# Raspberry_Pi_CM4_Periphery.net
KiCad netlist of a schematic drawn in Altium Designer
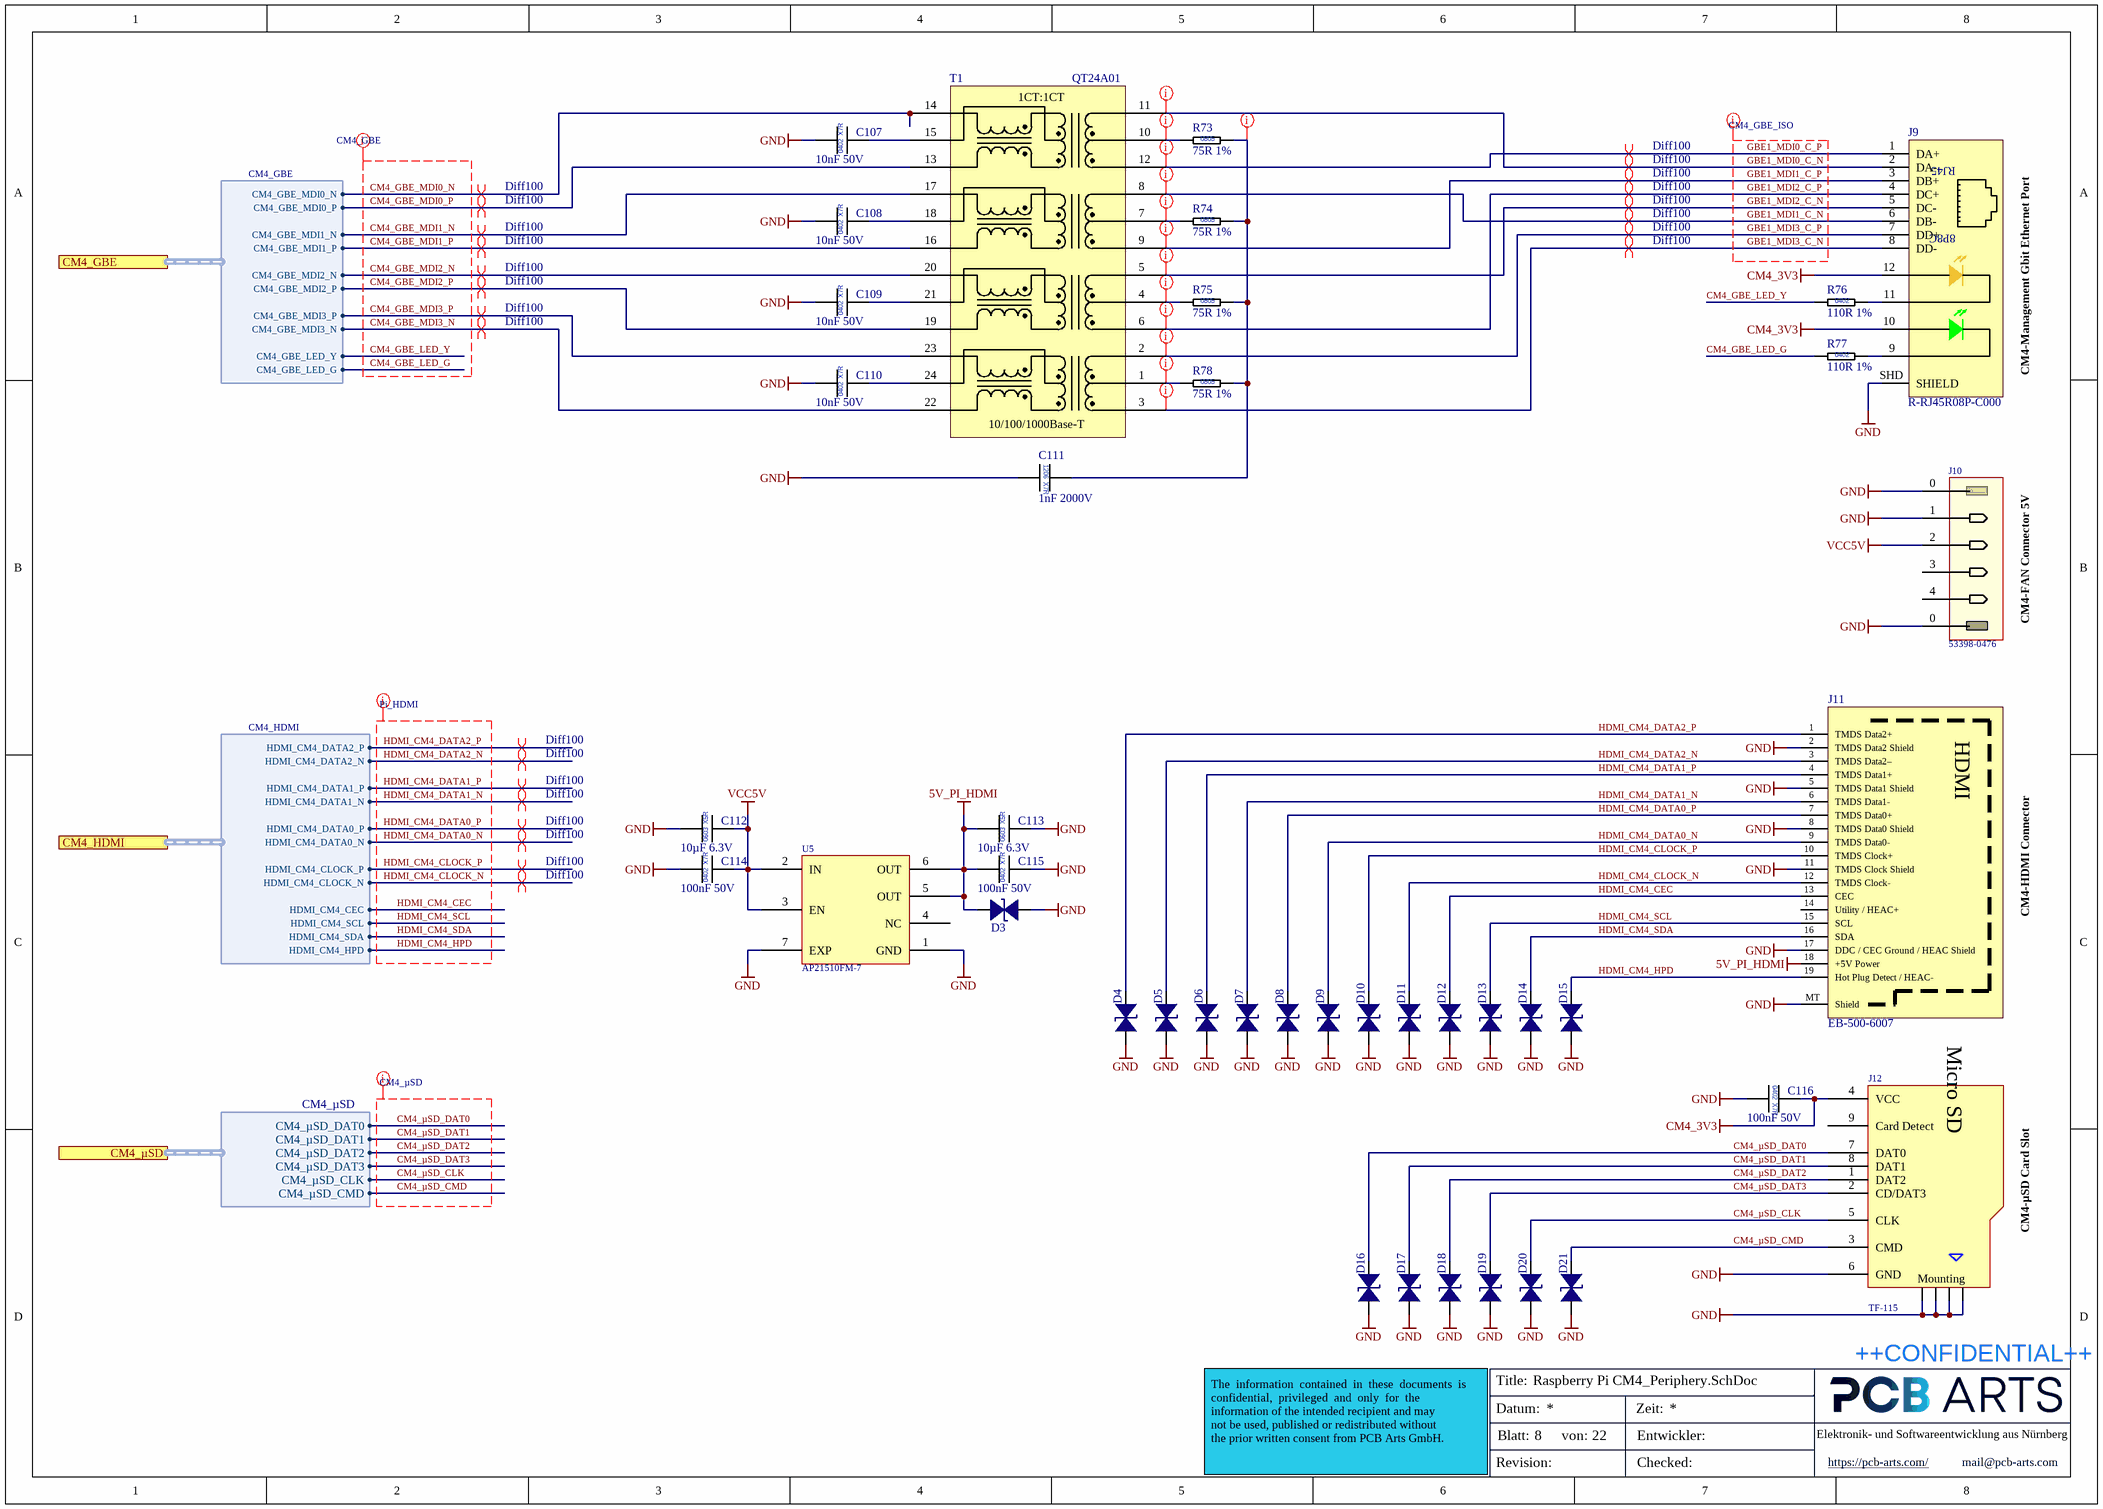
[diagram p0: Raspberry Pi CM4_Periphery.SchDoc]

(export (version "E")
  (design (tool "Eeschema 10.0.6"))
  (components
    (comp (ref "C107")
      (value "10nF 50V")
      (footprint "Cap:CAP_0402_L")
      (description "Multilayer Ceramic Capacitors MLCC - SMD/SMT 0402 50VDC")
      (libsource (lib "Cap") (part "CAP_0402_10nF_50V"))
    )
    (comp (ref "C108")
      (value "10nF 50V")
      (footprint "Cap:CAP_0402_L")
      (description "Multilayer Ceramic Capacitors MLCC - SMD/SMT 0402 50VDC")
      (libsource (lib "Cap") (part "CAP_0402_10nF_50V"))
    )
    (comp (ref "C109")
      (value "10nF 50V")
      (footprint "Cap:CAP_0402_L")
      (description "Multilayer Ceramic Capacitors MLCC - SMD/SMT 0402 50VDC")
      (libsource (lib "Cap") (part "CAP_0402_10nF_50V"))
    )
    (comp (ref "C110")
      (value "10nF 50V")
      (footprint "Cap:CAP_0402_L")
      (description "Multilayer Ceramic Capacitors MLCC - SMD/SMT 0402 50VDC")
      (libsource (lib "Cap") (part "CAP_0402_10nF_50V"))
    )
    (comp (ref "C111")
      (value "1nF 2000V")
      (footprint "Cap:CAP_1206")
      (description "Multilayer Ceramic Capacitors MLCC - SMD/SMT 1206 2000VDC")
      (libsource (lib "Cap") (part "CAP_1206_1nF_2000V"))
    )
    (comp (ref "C112")
      (value "10µF 6.3V")
      (footprint "Cap:CAP_0603_L")
      (description "Multilayer Ceramic Capacitors MLCC - SMD/SMT 0603 6.3VDC")
      (libsource (lib "Cap") (part "CAP_0603_10µF_6.3V"))
    )
    (comp (ref "C113")
      (value "10µF 6.3V")
      (footprint "Cap:CAP_0603_L")
      (description "Multilayer Ceramic Capacitors MLCC - SMD/SMT 0603 6.3VDC")
      (libsource (lib "Cap") (part "CAP_0603_10µF_6.3V"))
    )
    (comp (ref "C114")
      (value "100nF 50V")
      (footprint "Cap:CAP_0402_L")
      (description "Multilayer Ceramic Capacitors MLCC - SMD/SMT 0402 50VDC")
      (libsource (lib "Cap") (part "CAP_0402_100nF_50V"))
    )
    (comp (ref "C115")
      (value "100nF 50V")
      (footprint "Cap:CAP_0402_L")
      (description "Multilayer Ceramic Capacitors MLCC - SMD/SMT 0402 50VDC")
      (libsource (lib "Cap") (part "CAP_0402_100nF_50V"))
    )
    (comp (ref "C116")
      (value "100nF 50V")
      (footprint "Cap:CAP_0402_L")
      (description "Multilayer Ceramic Capacitors MLCC - SMD/SMT 0402 50VDC")
      (libsource (lib "") (part "CAP_0402_100nF_50V_1"))
    )
    (comp (ref "D3")
      (value "CESDP0402UC5VB")
      (footprint "Protec:TVS_0402")
      (description "Low Capacitance ESD Protection Diode 0402")
      (libsource (lib "Protec") (part "CESDP0402UC5VB_TVS Diode 0402"))
    )
    (comp (ref "D4")
      (value "CESDP0402UC5VB")
      (footprint "Protec:TVS_0402")
      (description "Low Capacitance ESD Protection Diode 0402")
      (libsource (lib "Protec") (part "CESDP0402UC5VB_TVS Diode 0402"))
    )
    (comp (ref "D5")
      (value "CESDP0402UC5VB")
      (footprint "Protec:TVS_0402")
      (description "Low Capacitance ESD Protection Diode 0402")
      (libsource (lib "Protec") (part "CESDP0402UC5VB_TVS Diode 0402"))
    )
    (comp (ref "D6")
      (value "CESDP0402UC5VB")
      (footprint "Protec:TVS_0402")
      (description "Low Capacitance ESD Protection Diode 0402")
      (libsource (lib "Protec") (part "CESDP0402UC5VB_TVS Diode 0402"))
    )
    (comp (ref "D7")
      (value "CESDP0402UC5VB")
      (footprint "Protec:TVS_0402")
      (description "Low Capacitance ESD Protection Diode 0402")
      (libsource (lib "Protec") (part "CESDP0402UC5VB_TVS Diode 0402"))
    )
    (comp (ref "D8")
      (value "CESDP0402UC5VB")
      (footprint "Protec:TVS_0402")
      (description "Low Capacitance ESD Protection Diode 0402")
      (libsource (lib "Protec") (part "CESDP0402UC5VB_TVS Diode 0402"))
    )
    (comp (ref "D9")
      (value "CESDP0402UC5VB")
      (footprint "Protec:TVS_0402")
      (description "Low Capacitance ESD Protection Diode 0402")
      (libsource (lib "Protec") (part "CESDP0402UC5VB_TVS Diode 0402"))
    )
    (comp (ref "D10")
      (value "CESDP0402UC5VB")
      (footprint "Protec:TVS_0402")
      (description "Low Capacitance ESD Protection Diode 0402")
      (libsource (lib "Protec") (part "CESDP0402UC5VB_TVS Diode 0402"))
    )
    (comp (ref "D11")
      (value "CESDP0402UC5VB")
      (footprint "Protec:TVS_0402")
      (description "Low Capacitance ESD Protection Diode 0402")
      (libsource (lib "Protec") (part "CESDP0402UC5VB_TVS Diode 0402"))
    )
    (comp (ref "D12")
      (value "CESDP0402UC5VB")
      (footprint "Protec:TVS_0402")
      (description "Low Capacitance ESD Protection Diode 0402")
      (libsource (lib "Protec") (part "CESDP0402UC5VB_TVS Diode 0402"))
    )
    (comp (ref "D13")
      (value "CESDP0402UC5VB")
      (footprint "Protec:TVS_0402")
      (description "Low Capacitance ESD Protection Diode 0402")
      (libsource (lib "Protec") (part "CESDP0402UC5VB_TVS Diode 0402"))
    )
    (comp (ref "D14")
      (value "CESDP0402UC5VB")
      (footprint "Protec:TVS_0402")
      (description "Low Capacitance ESD Protection Diode 0402")
      (libsource (lib "Protec") (part "CESDP0402UC5VB_TVS Diode 0402"))
    )
    (comp (ref "D15")
      (value "CESDP0402UC5VB")
      (footprint "Protec:TVS_0402")
      (description "Low Capacitance ESD Protection Diode 0402")
      (libsource (lib "Protec") (part "CESDP0402UC5VB_TVS Diode 0402"))
    )
    (comp (ref "D16")
      (value "CESDP0402UC5VB")
      (footprint "Protec:TVS_0402")
      (description "Low Capacitance ESD Protection Diode 0402")
      (libsource (lib "Protec") (part "CESDP0402UC5VB_TVS Diode 0402"))
    )
    (comp (ref "D17")
      (value "CESDP0402UC5VB")
      (footprint "Protec:TVS_0402")
      (description "Low Capacitance ESD Protection Diode 0402")
      (libsource (lib "Protec") (part "CESDP0402UC5VB_TVS Diode 0402"))
    )
    (comp (ref "D18")
      (value "CESDP0402UC5VB")
      (footprint "Protec:TVS_0402")
      (description "Low Capacitance ESD Protection Diode 0402")
      (libsource (lib "Protec") (part "CESDP0402UC5VB_TVS Diode 0402"))
    )
    (comp (ref "D19")
      (value "CESDP0402UC5VB")
      (footprint "Protec:TVS_0402")
      (description "Low Capacitance ESD Protection Diode 0402")
      (libsource (lib "Protec") (part "CESDP0402UC5VB_TVS Diode 0402"))
    )
    (comp (ref "D20")
      (value "CESDP0402UC5VB")
      (footprint "Protec:TVS_0402")
      (description "Low Capacitance ESD Protection Diode 0402")
      (libsource (lib "Protec") (part "CESDP0402UC5VB_TVS Diode 0402"))
    )
    (comp (ref "D21")
      (value "CESDP0402UC5VB")
      (footprint "Protec:TVS_0402")
      (description "Low Capacitance ESD Protection Diode 0402")
      (libsource (lib "Protec") (part "CESDP0402UC5VB_TVS Diode 0402"))
    )
    (comp (ref "J9")
      (value "R-RJ45R08P-C000")
      (footprint "Conn:Ckmtw - R-RJ45R08P-C000")
      (libsource (lib "Conn") (part "R-RJ45R08P-C000_RJ45 8P8C Shielded Yellow - Green Through Hole Ethernet Connectors"))
    )
    (comp (ref "J10")
      (value "53398-0476")
      (footprint "Conn:Molex 53398-0476")
      (description "1.25mm Pitch, PicoBlade PCB Header, Single Row, horizontal, SMD, 4 Pin")
      (libsource (lib "Conn") (part "53398-0476_1.25mm Pitch, PicoBlade PCB Header, Single Row, horizontal, SMD, 4 Pin"))
    )
    (comp (ref "J11")
      (value "EB-500-6007")
      (footprint "Conn:Elecbee EB-500-6007")
      (description "HDMI Connector Female Vertical 19 Pin")
      (libsource (lib "Conn") (part "EB-500-6007_HDMI Connector 19Pin Vertical THT"))
    )
    (comp (ref "J12")
      (value "TF-115")
      (footprint "conn:TF-115")
      (description "microSD™ Memory Card 8 connector&Ejector 14.5x14.75x1.85mm Card Sockets Connector")
      (libsource (lib "Conn") (part "TF-115_microSD™ Memory Card 8 connector"))
    )
    (comp (ref "R73")
      (value "75R 1%")
      (footprint "Res:RES_0805")
      (description "Thick Film Resistors - SMD 75Ohm 1%")
      (libsource (lib "Res") (part "RES_0805_75R_1%"))
    )
    (comp (ref "R74")
      (value "75R 1%")
      (footprint "Res:RES_0805")
      (description "Thick Film Resistors - SMD 75Ohm 1%")
      (libsource (lib "Res") (part "RES_0805_75R_1%"))
    )
    (comp (ref "R75")
      (value "75R 1%")
      (footprint "Res:RES_0805")
      (description "Thick Film Resistors - SMD 75Ohm 1%")
      (libsource (lib "Res") (part "RES_0805_75R_1%"))
    )
    (comp (ref "R76")
      (value "110R 1%")
      (footprint "Res:RES_0402_L")
      (description "Thick Film Resistors - SMD 110Ohm 1%")
      (libsource (lib "Res") (part "RES_0402_110R_1%"))
    )
    (comp (ref "R77")
      (value "110R 1%")
      (footprint "Res:RES_0402_L")
      (description "Thick Film Resistors - SMD 110Ohm 1%")
      (libsource (lib "Res") (part "RES_0402_110R_1%"))
    )
    (comp (ref "R78")
      (value "75R 1%")
      (footprint "Res:RES_0805")
      (description "Thick Film Resistors - SMD 75Ohm 1%")
      (libsource (lib "Res") (part "RES_0805_75R_1%"))
    )
    (comp (ref "T1")
      (value "QT24A01")
      (footprint "Indc:QT24A01")
      (description "1:1 350 28 1.2 -1 -16 SMD,24PIN RJ45 Transformer RoHS")
      (libsource (lib "Indc") (part "QT24A01_10/100/1000Base-T  Single  Port  Transformer"))
    )
    (comp (ref "U5")
      (value "AP21510FM-7")
      (footprint "Power:QFN50P201X181X60_HS-7N")
      (description "Power Switch ICs - Power Distribution 0.5A SGL Ch USB 2.0 Curr Limited Switch")
      (libsource (lib "Power") (part "AP21510FM-7_Power Switch ICs - Power Distribution Load Switch"))
    )
  )
  (nets
    (net (code "4") (name "/CM4_GBE_LED_G") (class "Default")
      (node (ref "R77") (pin "1") (pinfunction "1_1") (pintype "passive"))
    )
    (net (code "5") (name "/CM4_GBE_LED_Y") (class "Default")
      (node (ref "R76") (pin "1") (pinfunction "1_1") (pintype "passive"))
    )
    (net (code "6") (name "/CM4_GBE_MDI0_N") (class "Default")
      (node (ref "T1") (pin "14") (pinfunction "MX4+_14") (pintype "passive"))
    )
    (net (code "7") (name "/CM4_GBE_MDI0_P") (class "Default")
      (node (ref "T1") (pin "13") (pinfunction "MX4-_13") (pintype "passive"))
    )
    (net (code "8") (name "/CM4_GBE_MDI1_N") (class "Default")
      (node (ref "T1") (pin "17") (pinfunction "MX3+_17") (pintype "passive"))
    )
    (net (code "9") (name "/CM4_GBE_MDI1_P") (class "Default")
      (node (ref "T1") (pin "16") (pinfunction "MX3-_16") (pintype "passive"))
    )
    (net (code "10") (name "/CM4_GBE_MDI2_N") (class "Default")
      (node (ref "T1") (pin "20") (pinfunction "MX2+_20") (pintype "passive"))
    )
    (net (code "11") (name "/CM4_GBE_MDI2_P") (class "Default")
      (node (ref "T1") (pin "19") (pinfunction "MX2-_19") (pintype "passive"))
    )
    (net (code "12") (name "/CM4_GBE_MDI3_N") (class "Default")
      (node (ref "T1") (pin "22") (pinfunction "MX1-_22") (pintype "passive"))
    )
    (net (code "13") (name "/CM4_GBE_MDI3_P") (class "Default")
      (node (ref "T1") (pin "23") (pinfunction "MX1+_23") (pintype "passive"))
    )
    (net (code "14") (name "/CM4_µSD_CLK") (class "Default")
      (node (ref "D20") (pin "2") (pinfunction "2_2") (pintype "passive"))
      (node (ref "J12") (pin "5") (pinfunction "CLK_5") (pintype "passive"))
    )
    (net (code "15") (name "/CM4_µSD_CMD") (class "Default")
      (node (ref "D21") (pin "2") (pinfunction "2_2") (pintype "passive"))
      (node (ref "J12") (pin "3") (pinfunction "CMD_3") (pintype "passive"))
    )
    (net (code "16") (name "/CM4_µSD_DAT0") (class "Default")
      (node (ref "D16") (pin "2") (pinfunction "2_2") (pintype "passive"))
      (node (ref "J12") (pin "7") (pinfunction "DAT0_7") (pintype "passive"))
    )
    (net (code "17") (name "/CM4_µSD_DAT1") (class "Default")
      (node (ref "D17") (pin "2") (pinfunction "2_2") (pintype "passive"))
      (node (ref "J12") (pin "8") (pinfunction "DAT1_8") (pintype "passive"))
    )
    (net (code "18") (name "/CM4_µSD_DAT2") (class "Default")
      (node (ref "D18") (pin "2") (pinfunction "2_2") (pintype "passive"))
      (node (ref "J12") (pin "1") (pinfunction "DAT2_1") (pintype "passive"))
    )
    (net (code "19") (name "/CM4_µSD_DAT3") (class "Default")
      (node (ref "D19") (pin "2") (pinfunction "2_2") (pintype "passive"))
      (node (ref "J12") (pin "2") (pinfunction "CD/DAT3_2") (pintype "passive"))
    )
    (net (code "20") (name "/GBE1_MDI0_C_N") (class "Default")
      (node (ref "J9") (pin "2") (pinfunction "DA-_2") (pintype "passive"))
      (node (ref "T1") (pin "11") (pinfunction "TD4+_11") (pintype "passive"))
    )
    (net (code "21") (name "/GBE1_MDI0_C_P") (class "Default")
      (node (ref "J9") (pin "1") (pinfunction "DA+_1") (pintype "passive"))
      (node (ref "T1") (pin "12") (pinfunction "TD4-_12") (pintype "passive"))
    )
    (net (code "22") (name "/GBE1_MDI1_C_N") (class "Default")
      (node (ref "J9") (pin "6") (pinfunction "DB-_6") (pintype "passive"))
      (node (ref "T1") (pin "8") (pinfunction "TD3+_8") (pintype "passive"))
    )
    (net (code "23") (name "/GBE1_MDI1_C_P") (class "Default")
      (node (ref "J9") (pin "3") (pinfunction "DB+_3") (pintype "passive"))
      (node (ref "T1") (pin "9") (pinfunction "TD3-_9") (pintype "passive"))
    )
    (net (code "24") (name "/GBE1_MDI2_C_N") (class "Default")
      (node (ref "J9") (pin "5") (pinfunction "DC-_5") (pintype "passive"))
      (node (ref "T1") (pin "5") (pinfunction "TD2+_5") (pintype "passive"))
    )
    (net (code "25") (name "/GBE1_MDI2_C_P") (class "Default")
      (node (ref "J9") (pin "4") (pinfunction "DC+_4") (pintype "passive"))
      (node (ref "T1") (pin "6") (pinfunction "TD2-_6") (pintype "passive"))
    )
    (net (code "26") (name "/GBE1_MDI3_C_N") (class "Default")
      (node (ref "J9") (pin "8") (pinfunction "DD-_8") (pintype "passive"))
      (node (ref "T1") (pin "3") (pinfunction "TD1-_3") (pintype "passive"))
    )
    (net (code "27") (name "/GBE1_MDI3_C_P") (class "Default")
      (node (ref "J9") (pin "7") (pinfunction "DD+_7") (pintype "passive"))
      (node (ref "T1") (pin "2") (pinfunction "TD1+_2") (pintype "passive"))
    )
    (net (code "28") (name "/HDMI_CM4_CEC") (class "Default")
      (node (ref "D12") (pin "2") (pinfunction "2_2") (pintype "passive"))
      (node (ref "J11") (pin "13") (pinfunction "CEC_13") (pintype "passive"))
    )
    (net (code "29") (name "/HDMI_CM4_CLOCK_N") (class "Default")
      (node (ref "D11") (pin "2") (pinfunction "2_2") (pintype "passive"))
      (node (ref "J11") (pin "12") (pinfunction "TMDS_Clock-_12") (pintype "passive"))
    )
    (net (code "30") (name "/HDMI_CM4_CLOCK_P") (class "Default")
      (node (ref "D10") (pin "2") (pinfunction "2_2") (pintype "passive"))
      (node (ref "J11") (pin "10") (pinfunction "TMDS_Clock+_10") (pintype "passive"))
    )
    (net (code "31") (name "/HDMI_CM4_DATA0_N") (class "Default")
      (node (ref "D9") (pin "2") (pinfunction "2_2") (pintype "passive"))
      (node (ref "J11") (pin "9") (pinfunction "TMDS_Data0-_9") (pintype "passive"))
    )
    (net (code "32") (name "/HDMI_CM4_DATA0_P") (class "Default")
      (node (ref "D8") (pin "2") (pinfunction "2_2") (pintype "passive"))
      (node (ref "J11") (pin "7") (pinfunction "TMDS_Data0+_7") (pintype "passive"))
    )
    (net (code "33") (name "/HDMI_CM4_DATA1_N") (class "Default")
      (node (ref "D7") (pin "2") (pinfunction "2_2") (pintype "passive"))
      (node (ref "J11") (pin "6") (pinfunction "TMDS_Data1-_6") (pintype "passive"))
    )
    (net (code "34") (name "/HDMI_CM4_DATA1_P") (class "Default")
      (node (ref "D6") (pin "2") (pinfunction "2_2") (pintype "passive"))
      (node (ref "J11") (pin "4") (pinfunction "TMDS_Data1+_4") (pintype "passive"))
    )
    (net (code "35") (name "/HDMI_CM4_DATA2_N") (class "Default")
      (node (ref "D5") (pin "2") (pinfunction "2_2") (pintype "passive"))
      (node (ref "J11") (pin "3") (pinfunction "TMDS_Data2–_3") (pintype "passive"))
    )
    (net (code "36") (name "/HDMI_CM4_DATA2_P") (class "Default")
      (node (ref "D4") (pin "2") (pinfunction "2_2") (pintype "passive"))
      (node (ref "J11") (pin "1") (pinfunction "TMDS_Data2+_1") (pintype "passive"))
    )
    (net (code "37") (name "/HDMI_CM4_HPD") (class "Default")
      (node (ref "D15") (pin "2") (pinfunction "2_2") (pintype "passive"))
      (node (ref "J11") (pin "19") (pinfunction "Hot_Plug_Detect_/_HEAC-_19") (pintype "passive"))
    )
    (net (code "38") (name "/HDMI_CM4_SCL") (class "Default")
      (node (ref "D13") (pin "2") (pinfunction "2_2") (pintype "passive"))
      (node (ref "J11") (pin "15") (pinfunction "SCL_15") (pintype "passive"))
    )
    (net (code "39") (name "/HDMI_CM4_SDA") (class "Default")
      (node (ref "D14") (pin "2") (pinfunction "2_2") (pintype "passive"))
      (node (ref "J11") (pin "16") (pinfunction "SDA_16") (pintype "passive"))
    )
    (net (code "43") (name "5V_PI_HDMI") (class "Default")
      (node (ref "C113") (pin "1") (pinfunction "1_1") (pintype "passive"))
      (node (ref "C115") (pin "1") (pinfunction "1_1") (pintype "passive"))
      (node (ref "D3") (pin "1") (pinfunction "1_1") (pintype "passive"))
      (node (ref "J11") (pin "18") (pinfunction "+5V_Power_18") (pintype "passive"))
      (node (ref "U5") (pin "5") (pinfunction "OUT_5") (pintype "power_in"))
      (node (ref "U5") (pin "6") (pinfunction "OUT_6") (pintype "power_in"))
    )
    (net (code "44") (name "CM4_3V3") (class "Default")
      (node (ref "C116") (pin "1") (pinfunction "1_1") (pintype "passive"))
      (node (ref "J12") (pin "4") (pinfunction "VCC_4") (pintype "passive"))
      (node (ref "J9") (pin "10") (pinfunction "10_10") (pintype "passive"))
      (node (ref "J9") (pin "12") (pinfunction "12_12") (pintype "passive"))
    )
    (net (code "45") (name "GND") (class "Default")
      (node (ref "C107") (pin "1") (pinfunction "1_1") (pintype "passive"))
      (node (ref "C108") (pin "1") (pinfunction "1_1") (pintype "passive"))
      (node (ref "C109") (pin "1") (pinfunction "1_1") (pintype "passive"))
      (node (ref "C110") (pin "1") (pinfunction "1_1") (pintype "passive"))
      (node (ref "C111") (pin "2") (pinfunction "2_2") (pintype "passive"))
      (node (ref "C112") (pin "1") (pinfunction "1_1") (pintype "passive"))
      (node (ref "C113") (pin "2") (pinfunction "2_2") (pintype "passive"))
      (node (ref "C114") (pin "1") (pinfunction "1_1") (pintype "passive"))
      (node (ref "C115") (pin "2") (pinfunction "2_2") (pintype "passive"))
      (node (ref "C116") (pin "2") (pinfunction "2_2") (pintype "passive"))
      (node (ref "D10") (pin "1") (pinfunction "1_1") (pintype "passive"))
      (node (ref "D11") (pin "1") (pinfunction "1_1") (pintype "passive"))
      (node (ref "D12") (pin "1") (pinfunction "1_1") (pintype "passive"))
      (node (ref "D13") (pin "1") (pinfunction "1_1") (pintype "passive"))
      (node (ref "D14") (pin "1") (pinfunction "1_1") (pintype "passive"))
      (node (ref "D15") (pin "1") (pinfunction "1_1") (pintype "passive"))
      (node (ref "D16") (pin "1") (pinfunction "1_1") (pintype "passive"))
      (node (ref "D17") (pin "1") (pinfunction "1_1") (pintype "passive"))
      (node (ref "D18") (pin "1") (pinfunction "1_1") (pintype "passive"))
      (node (ref "D19") (pin "1") (pinfunction "1_1") (pintype "passive"))
      (node (ref "D20") (pin "1") (pinfunction "1_1") (pintype "passive"))
      (node (ref "D21") (pin "1") (pinfunction "1_1") (pintype "passive"))
      (node (ref "D3") (pin "2") (pinfunction "2_2") (pintype "passive"))
      (node (ref "D4") (pin "1") (pinfunction "1_1") (pintype "passive"))
      (node (ref "D5") (pin "1") (pinfunction "1_1") (pintype "passive"))
      (node (ref "D6") (pin "1") (pinfunction "1_1") (pintype "passive"))
      (node (ref "D7") (pin "1") (pinfunction "1_1") (pintype "passive"))
      (node (ref "D8") (pin "1") (pinfunction "1_1") (pintype "passive"))
      (node (ref "D9") (pin "1") (pinfunction "1_1") (pintype "passive"))
      (node (ref "J10") (pin "0") (pinfunction "0_0") (pintype "passive"))
      (node (ref "J10") (pin "1") (pinfunction "1_1") (pintype "passive"))
      (node (ref "J11") (pin "11") (pinfunction "TMDS_Clock_Shield_11") (pintype "passive"))
      (node (ref "J11") (pin "17") (pinfunction "DDC_/_CEC_Ground_/_HEAC_Shield_17") (pintype "passive"))
      (node (ref "J11") (pin "2") (pinfunction "TMDS_Data2_Shield_2") (pintype "passive"))
      (node (ref "J11") (pin "5") (pinfunction "TMDS_Data1_Shield_5") (pintype "passive"))
      (node (ref "J11") (pin "8") (pinfunction "TMDS_Data0_Shield_8") (pintype "passive"))
      (node (ref "J11") (pin "MT") (pinfunction "Shield_MT") (pintype "passive"))
      (node (ref "J12") (pin "10") (pinfunction "10_10") (pintype "passive"))
      (node (ref "J12") (pin "11") (pinfunction "11_11") (pintype "passive"))
      (node (ref "J12") (pin "12") (pinfunction "12_12") (pintype "passive"))
      (node (ref "J12") (pin "13") (pinfunction "13_13") (pintype "passive"))
      (node (ref "J12") (pin "6") (pinfunction "GND_6") (pintype "passive"))
      (node (ref "J9") (pin "SHD") (pinfunction "SHIELD_SHD") (pintype "passive"))
      (node (ref "U5") (pin "1") (pinfunction "GND_1") (pintype "power_in"))
      (node (ref "U5") (pin "7") (pinfunction "EXP_7") (pintype "power_in"))
    )
    (net (code "46") (name "Net-(C111-Pad1)") (class "Default")
      (node (ref "C111") (pin "1") (pinfunction "1_1") (pintype "passive"))
      (node (ref "R73") (pin "2") (pinfunction "2_2") (pintype "passive"))
      (node (ref "R74") (pin "2") (pinfunction "2_2") (pintype "passive"))
      (node (ref "R75") (pin "2") (pinfunction "2_2") (pintype "passive"))
      (node (ref "R78") (pin "2") (pinfunction "2_2") (pintype "passive"))
    )
    (net (code "47") (name "Net-(J9-Pad9)") (class "Default")
      (node (ref "J9") (pin "9") (pinfunction "9_9") (pintype "passive"))
      (node (ref "R77") (pin "2") (pinfunction "2_2") (pintype "passive"))
    )
    (net (code "48") (name "Net-(J9-Pad11)") (class "Default")
      (node (ref "J9") (pin "11") (pinfunction "11_11") (pintype "passive"))
      (node (ref "R76") (pin "2") (pinfunction "2_2") (pintype "passive"))
    )
    (net (code "49") (name "Net-(T1-MCT1)") (class "Default")
      (node (ref "C110") (pin "2") (pinfunction "2_2") (pintype "passive"))
      (node (ref "T1") (pin "24") (pinfunction "MCT1_24") (pintype "passive"))
    )
    (net (code "50") (name "Net-(T1-MCT2)") (class "Default")
      (node (ref "C109") (pin "2") (pinfunction "2_2") (pintype "passive"))
      (node (ref "T1") (pin "21") (pinfunction "MCT2_21") (pintype "passive"))
    )
    (net (code "51") (name "Net-(T1-MCT3)") (class "Default")
      (node (ref "C108") (pin "2") (pinfunction "2_2") (pintype "passive"))
      (node (ref "T1") (pin "18") (pinfunction "MCT3_18") (pintype "passive"))
    )
    (net (code "52") (name "Net-(T1-MCT4)") (class "Default")
      (node (ref "C107") (pin "2") (pinfunction "2_2") (pintype "passive"))
      (node (ref "T1") (pin "15") (pinfunction "MCT4_15") (pintype "passive"))
    )
    (net (code "53") (name "Net-(T1-TCT1)") (class "Default")
      (node (ref "R78") (pin "1") (pinfunction "1_1") (pintype "passive"))
      (node (ref "T1") (pin "1") (pinfunction "TCT1_1") (pintype "passive"))
    )
    (net (code "54") (name "Net-(T1-TCT2)") (class "Default")
      (node (ref "R75") (pin "1") (pinfunction "1_1") (pintype "passive"))
      (node (ref "T1") (pin "4") (pinfunction "TCT2_4") (pintype "passive"))
    )
    (net (code "55") (name "Net-(T1-TCT3)") (class "Default")
      (node (ref "R74") (pin "1") (pinfunction "1_1") (pintype "passive"))
      (node (ref "T1") (pin "7") (pinfunction "TCT3_7") (pintype "passive"))
    )
    (net (code "56") (name "Net-(T1-TCT4)") (class "Default")
      (node (ref "R73") (pin "1") (pinfunction "1_1") (pintype "passive"))
      (node (ref "T1") (pin "10") (pinfunction "TCT4_10") (pintype "passive"))
    )
    (net (code "57") (name "VCC5V") (class "Default")
      (node (ref "C112") (pin "2") (pinfunction "2_2") (pintype "passive"))
      (node (ref "C114") (pin "2") (pinfunction "2_2") (pintype "passive"))
      (node (ref "J10") (pin "2") (pinfunction "2_2") (pintype "passive"))
      (node (ref "U5") (pin "2") (pinfunction "IN_2") (pintype "power_in"))
      (node (ref "U5") (pin "3") (pinfunction "EN_3") (pintype "power_in"))
    )
    (net (code "58") (name "unconnected-(J10-Pad3)") (class "Default")
      (node (ref "J10") (pin "3") (pinfunction "3_3") (pintype "passive"))
    )
    (net (code "59") (name "unconnected-(J10-Pad4)") (class "Default")
      (node (ref "J10") (pin "4") (pinfunction "4_4") (pintype "passive"))
    )
    (net (code "60") (name "unconnected-(J11-Utility_{slash}_HEAC+-Pad14)") (class "Default")
      (node (ref "J11") (pin "14") (pinfunction "Utility_/_HEAC+_14") (pintype "passive"))
    )
    (net (code "61") (name "unconnected-(J12-Card_Detect-Pad9)") (class "Default")
      (node (ref "J12") (pin "9") (pinfunction "Card_Detect_9") (pintype "passive"))
    )
    (net (code "62") (name "unconnected-(U5-NC-Pad4)") (class "Default")
      (node (ref "U5") (pin "4") (pinfunction "NC_4") (pintype "power_in"))
    )
  )
)
